# Power_Supply.net
KiCad netlist of a schematic drawn in Altium Designer
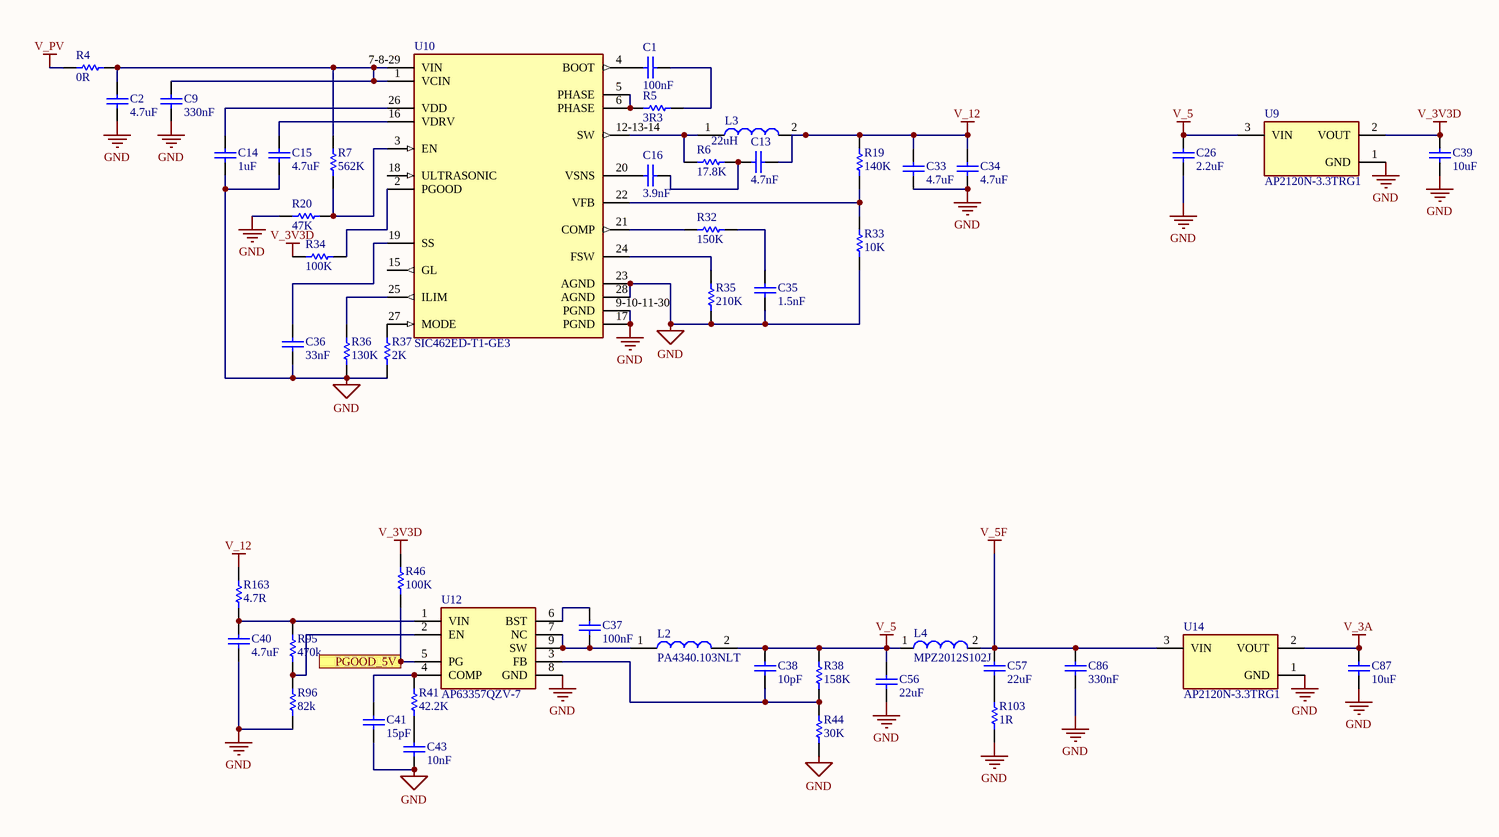
[diagram p0: Power_Supply.SchDoc]

(export (version "E")
  (design (tool "Eeschema 10.0.6"))
  (components
    (comp (ref "C1")
      (value "100nF")
      (footprint "CAPC1005X56X25NL10T15")
      (fields
        (field (name "MANUFACTURER") "AVX Interconnect / Elco")
        (field (name "PART NUMBER") "0402YC104KAT2A")
        (field (name "TOLERANCE") "10%")
      )
      (libsource (lib "Altium Content Vault") (part "CAP"))
    )
    (comp (ref "C2")
      (value "4.7uF")
      (footprint "CAPC3216X180X50NL20T25")
      (description "Chip Capacitor, 4.7 uF, +/- 10%, 50 V, -55 to 125 degC, 1206 (3216 Metric), RoHS, Tape and Reel")
      (fields (field (name "TOLERANCE") "10%") (field (name "MANUFACTURER") "AVX"))
      (libsource (lib "Altium Content Vault") (part "CAP-NP-2"))
    )
    (comp (ref "C9")
      (value "330nF")
      (footprint "CAPC2013X140X50NL20T25")
      (description "C0805C224K1RACAUTO")
      (fields (field (name "MANUFACTURER") "Kemet") (field (name "TOLERANCE") "10%"))
      (libsource (lib "Altium Content Vault") (part "CAP"))
    )
    (comp (ref "C13")
      (value "4.7nF")
      (footprint "CAPC1608X90X35NL10T15")
      (description "CAP CER 4700PF 50V X7R 0603")
      (fields (field (name "PART NUMBER") "GRM188R71H472KA01D") (field (name "MANUFACTURER") "Murata"))
      (libsource (lib "Altium Content Vault") (part "CAP"))
    )
    (comp (ref "C14")
      (value "1uF")
      (footprint "CAPC1608X90X35NL15T15")
      (description "SMD, 1 µF, 10 V, 0603 [Metrisch 1608], ± 10%, X7R")
      (fields (field (name "MANUFACTURER") "Kemet") (field (name "PART NUMBER") "C0603C105K8RACTU"))
      (libsource (lib "Altium Content Vault") (part "CAP"))
    )
    (comp (ref "C15")
      (value "4.7uF")
      (footprint "CAPC2013X152X50NL20T25")
      (fields
        (field (name "PART NUMBER") "0805YC475KAT2A")
        (field (name "MANUFACTURER") "AVX Interconnect / Elco")
        (field (name "TOLERANCE") "10%")
      )
      (libsource (lib "Altium Content Vault") (part "CAP"))
    )
    (comp (ref "C16")
      (value "3.9nF")
      (footprint "CAPC1608X90X35NL15T15")
      (fields
        (field (name "PART NUMBER") "06031C392KAT2A")
        (field (name "MANUFACTURER") "AVX Interconnect / Elco")
        (field (name "TOLERANCE") "10%")
      )
      (libsource (lib "Altium Content Vault") (part "CAP"))
    )
    (comp (ref "C26")
      (value "2.2uF")
      (footprint "CAPC2013X140X45NL15T25")
      (fields (field (name "PART NUMBER") "GRM21BR71A106KE51L") (field (name "MANUFACTURER") "Murata"))
      (libsource (lib "Altium Content Vault") (part "CAP"))
    )
    (comp (ref "C33")
      (value "4.7uF")
      (footprint "CAPC3216X180X50NL20T25")
      (description "Chip Capacitor, 4.7 uF, +/- 10%, 50 V, -55 to 125 degC, 1206 (3216 Metric), RoHS, Tape and Reel")
      (fields (field (name "TOLERANCE") "10%") (field (name "MANUFACTURER") "AVX"))
      (libsource (lib "Altium Content Vault") (part "CAP-NP-2"))
    )
    (comp (ref "C34")
      (value "4.7uF")
      (footprint "CAPC3216X180X50NL20T25")
      (description "Chip Capacitor, 4.7 uF, +/- 10%, 50 V, -55 to 125 degC, 1206 (3216 Metric), RoHS, Tape and Reel")
      (fields (field (name "TOLERANCE") "10%") (field (name "MANUFACTURER") "AVX"))
      (libsource (lib "Altium Content Vault") (part "CAP-NP-2"))
    )
    (comp (ref "C35")
      (value "1.5nF")
      (footprint "CAPC1608X90X35NL15T15")
      (fields
        (field (name "PART NUMBER") "06031C152JAT2A")
        (field (name "MANUFACTURER") "AVX Interconnect / Elco")
        (field (name "TOLERANCE") "5%")
      )
      (libsource (lib "Altium Content Vault") (part "CAP"))
    )
    (comp (ref "C36")
      (value "33nF")
      (footprint "CAPC1005X55X25NL05T10")
      (fields
        (field (name "PART NUMBER") "GRM155R71E333KA88D")
        (field (name "MANUFACTURER") "Murata")
        (field (name "TOLERANCE") "10%")
      )
      (libsource (lib "Altium Content Vault") (part "CAP"))
    )
    (comp (ref "C37")
      (value "100nF")
      (footprint "CAPC1005X56X25NL10T15")
      (fields
        (field (name "MANUFACTURER") "AVX Interconnect / Elco")
        (field (name "PART NUMBER") "0402YC104KAT2A")
        (field (name "TOLERANCE") "10%")
      )
      (libsource (lib "Altium Content Vault") (part "CAP"))
    )
    (comp (ref "C38")
      (value "10pF")
      (footprint "CAPC1005X56X25NL10T15")
      (fields
        (field (name "PART NUMBER") "04025A100DAT2A")
        (field (name "MANUFACTURER") "AVX Interconnect / Elco")
        (field (name "TOLERANCE") "5%")
      )
      (libsource (lib "Altium Content Vault") (part "CAP"))
    )
    (comp (ref "C39")
      (value "10uF")
      (footprint "CAPC2013X140X45NL15T25")
      (fields (field (name "PART NUMBER") "GRM21BR71A106KE51L") (field (name "MANUFACTURER") "Murata"))
      (libsource (lib "Altium Content Vault") (part "CAP"))
    )
    (comp (ref "C40")
      (value "4.7uF")
      (footprint "CAPC3216X180X50NL20T25")
      (description "Chip Capacitor, 4.7 uF, +/- 10%, 50 V, -55 to 125 degC, 1206 (3216 Metric), RoHS, Tape and Reel")
      (fields (field (name "TOLERANCE") "10%") (field (name "MANUFACTURER") "AVX"))
      (libsource (lib "Altium Content Vault") (part "CAP-NP-2"))
    )
    (comp (ref "C41")
      (value "15pF")
      (footprint "CAPC1005X56X25NL10T15")
      (description "Cap Ceramic 15pF 50V C0G 1% SMD 0402 125C Paper T/R")
      (fields
        (field (name "MANUFACTURER") "AVX Interconnect / Elco")
        (field (name "PART NUMBER") "04025A150FAT2A")
      )
      (libsource (lib "Altium Content Vault") (part "CAP"))
    )
    (comp (ref "C43")
      (value "10nF")
      (footprint "CAPC1005X56X25NL10T15")
      (fields
        (field (name "MANUFACTURER") "AVX Interconnect / Elco")
        (field (name "PART NUMBER") "04023C103JAT2A")
        (field (name "TOLERANCE") "5%")
      )
      (libsource (lib "Altium Content Vault") (part "CAP"))
    )
    (comp (ref "C56")
      (value "22uF")
      (footprint "CAPC1206(3216)190_N")
      (description "CAP 22uF 6.3V ±10% 1206 (3216 Metric) Thickness 1.9mm SMD")
      (fields (field (name "TOLERANCE") "Â±10%") (field (name "MANUFACTURER") "Kyocera AVX"))
      (libsource (lib "Altium Content Vault") (part "CAP"))
    )
    (comp (ref "C57")
      (value "22uF")
      (footprint "CAPC1206(3216)190_M")
      (description "CAP 22uF 6.3V ±10% 1206 (3216 Metric) Thickness 1.9mm SMD")
      (fields (field (name "TOLERANCE") "Â±10%") (field (name "MANUFACTURER") "Kyocera AVX"))
      (libsource (lib "Altium Content Vault") (part "CAP"))
    )
    (comp (ref "C86")
      (value "330nF")
      (footprint "CAPC2013X140X45NL15T25")
      (fields (field (name "PART NUMBER") "GRM21BR71A106KE51L") (field (name "MANUFACTURER") "Murata"))
      (libsource (lib "Altium Content Vault") (part "CAP"))
    )
    (comp (ref "C87")
      (value "10uF")
      (footprint "CAPC2013X140X45NL15T25")
      (fields (field (name "PART NUMBER") "GRM21BR71A106KE51L") (field (name "MANUFACTURER") "Murata"))
      (libsource (lib "Altium Content Vault") (part "CAP"))
    )
    (comp (ref "L2")
      (value "PA4340.103NLT")
      (footprint "SamacSys:INDPM6054X300N")
      (description "Inductor 10uH")
      (fields (field (name "ARROW PART NUMBER") "PA4340.472NLT"))
      (libsource (lib "*") (part "PA4340.472NLT"))
    )
    (comp (ref "L3")
      (value "22uH")
      (footprint "SamacSys:INDPM8680X400N")
      (description "Inductor 22uH")
      (fields
        (field (name "MANUFACTURER_PART_NUMBER") "MPX1D0840L220")
        (field (name "MOUSER PART NUMBER") "80-MPX1D0840L220")
      )
      (libsource (lib "*") (part "MPX1D0840L470"))
    )
    (comp (ref "L4")
      (value "MPZ2012S102J")
      (footprint "SMD-0805")
      (description "SMD EMI Suppression Ferrite Bead WE-CBF, Z = 1500 Ohm")
      (libsource (lib "Altium Content Vault") (part "PAS-IND-INDUCTOR-2"))
    )
    (comp (ref "R4")
      (value "0R")
      (footprint "RESC1608X55X25ML10T15")
      (description "Chip Resistor, 0 Ohm, +/- 5%, 0.1 W, -55 to 155 degC, 0603 (1608 Metric), RoHS, Tape and Reel")
      (fields (field (name "TOLERANCE") "5%") (field (name "MANUFACTURER") "Yageo"))
      (libsource (lib "Altium Content Vault") (part "RES-2"))
    )
    (comp (ref "R5")
      (value "3R3")
      (footprint "RESC1005X40X25NL05T10")
      (description "Res Thick Film 0402 3.3 Ohm 1% 1/16W ±200ppm/°C Molded SMD Paper T/R")
      (fields (field (name "MANUFACTURER") "Yageo / Phycomp") (field (name "PART NUMBER") "RC0402FR-073R3L"))
      (libsource (lib "Altium Content Vault") (part "RES"))
    )
    (comp (ref "R6")
      (value "17.8K")
      (footprint "RESC1608X55X30NL15T15")
      (description "RESISTOR, THICK FILM, 17.8KOHM, 0603, 100mW, ± 1%")
      (fields (field (name "PART NUMBER") "ERJ-3EKF1782V") (field (name "MANUFACTURER") "Panasonic"))
      (libsource (lib "Altium Content Vault") (part "RES"))
    )
    (comp (ref "R7")
      (value "562K")
      (footprint "RESC1609X50X30NL10T20")
      (description "RES, THICK FILM, 562K, 1%, 0.1W, 0603")
      (fields (field (name "PART NUMBER") "CRCW0603562KFKEA") (field (name "MANUFACTURER") "Vishay Dale"))
      (libsource (lib "Altium Content Vault") (part "RES"))
    )
    (comp (ref "R19")
      (value "140K")
      (footprint "RESC1005X40X25NL05T05")
      (description "SMD Chip Resistor, 0402 [1005 Metric], 140 kohm, ERJ2R Series, 50 V, Thick Film, 100 mW, 1%")
      (fields (field (name "PART NUMBER") "ERJ-2RKF1403X") (field (name "MANUFACTURER") "Panasonic"))
      (libsource (lib "Altium Content Vault") (part "RES"))
    )
    (comp (ref "R20")
      (value "47K")
      (footprint "RESC1608X55X30NL15T15")
      (description "Chip Resistor, 47 KOhm, +/- 1%, 0.1 W, -55 to 155 degC, 0603 (1608 Metric), RoHS, Tape and Reel")
      (fields
        (field (name "MANUFACTURER") "Panasonic")
        (field (name "MANUFACTURER PART NUMBER") "ERJ3EKF4702V")
      )
      (libsource (lib "Altium Content Vault") (part "RES-2"))
    )
    (comp (ref "R32")
      (value "150K")
      (footprint "RESC1005X40X25NL05T05")
      (description "RES, THICK FILM, 150K, 1%, 0.1W, 0402")
      (fields (field (name "MANUFACTURER") "Panasonic") (field (name "PART NUMBER") "ERJ-2RKF1503X"))
      (libsource (lib "Altium Content Vault") (part "RES"))
    )
    (comp (ref "R33")
      (value "10K")
      (footprint "RESC1005X40X25NL05T05")
      (description "Chip Resistor, 10 KOhm, +/- 1%, 0.1 W, -55 to 155 degC, 0402 (1005 Metric), RoHS, Tape and Reel")
      (fields (field (name "TOLERANCE") "1%") (field (name "MANUFACTURER") "Panasonic"))
      (libsource (lib "Altium Content Vault") (part "RES-2"))
    )
    (comp (ref "R34")
      (value "100K")
      (footprint "RESC1005X40X25NL05T10")
      (description "Res General Purpose Thick Film 0402 100K Ohm 1% 1/16W ±100ppm/°C Molded SMD Paper T/R")
      (fields (field (name "PART NUMBER") "RC0402FR-07100KL") (field (name "MANUFACTURER") "Yageo / Phycomp"))
      (libsource (lib "Altium Content Vault") (part "RES"))
    )
    (comp (ref "R35")
      (value "210K")
      (footprint "RESC1005X40X25NL05T05")
      (description "SMD Chip Resistor, Thick Film, 210 kohm, 50 V, 0402 [1005 Metric], 100 mW,  1%, ERJ2R Series")
      (fields (field (name "MANUFACTURER") "Panasonic") (field (name "PART NUMBER") "ERJ-2RKF2103X"))
      (libsource (lib "Altium Content Vault") (part "RES"))
    )
    (comp (ref "R36")
      (value "130K")
      (footprint "RESC1005X40X25NL05T10")
      (description "Res Thick Film 1.0 x 0.5 mm 130K Ohm 1% 0.063W(1/16W) 100ppm/ C Molded SMD Paper T/R")
      (fields (field (name "PART NUMBER") "RC0402FR-07130KL") (field (name "MANUFACTURER") "Yageo / Phycomp"))
      (libsource (lib "Altium Content Vault") (part "RES"))
    )
    (comp (ref "R37")
      (value "2K")
      (footprint "RESC1005X40X25NL05T05")
      (description "Chip Resistor, 2 KOhm, +/- 1%, 100 mW, -55 to 155 degC, 0402 (1005 Metric), RoHS, Tape and Reel")
      (fields (field (name "MANUFACTURER") "Basic Passives") (field (name "TOLERANCE") "1%"))
      (libsource (lib "Altium Content Vault") (part "RES-2"))
    )
    (comp (ref "R38")
      (value "158K")
      (footprint "RESC1005X40X25NL05T05")
      (description "RES SMD 158K OHM 1% 1/16W 0402")
      (fields (field (name "MANUFACTURER") "Vishay Dale") (field (name "PART NUMBER") "CRCW0402158KFKTD"))
      (libsource (lib "Altium Content Vault") (part "RES"))
    )
    (comp (ref "R41")
      (value "42.2K")
      (footprint "RESC1005X40X25NL05T05")
      (description "Surface Mount Chip Resistor, Thick Film, AEC-Q200 CRCW Series, 42.2 kohm, 63 mW,  1%, 50 V")
      (fields (field (name "PART NUMBER") "CRCW040242K2FKED") (field (name "MANUFACTURER") "Vishay Dale"))
      (libsource (lib "Altium Content Vault") (part "RES"))
    )
    (comp (ref "R44")
      (value "30K")
      (footprint "RESC1005X40X25NL05T05")
      (description "Res Thick Film 0402 30K Ohm 1% 0.063W(1/16W) ±100ppm/C Molded SMD Automotive Paper T/R")
      (fields (field (name "PART NUMBER") "CRCW040230K0FKED") (field (name "MANUFACTURER") "Vishay Dale"))
      (libsource (lib "Altium Content Vault") (part "RES"))
    )
    (comp (ref "R46")
      (value "100K")
      (footprint "RESC1005X40X25NL05T10")
      (description "Res General Purpose Thick Film 0402 100K Ohm 1% 1/16W ±100ppm/°C Molded SMD Paper T/R")
      (fields (field (name "PART NUMBER") "RC0402FR-07100KL") (field (name "MANUFACTURER") "Yageo / Phycomp"))
      (libsource (lib "Altium Content Vault") (part "RES"))
    )
    (comp (ref "R95")
      (value "470k")
      (footprint "RESC1005X40X25NL05T05")
      (description "ERJ-2RKF4993X")
      (fields (field (name "MANUFACTURER") "Panasonic") (field (name "TOLERANCE") "1%"))
      (libsource (lib "Altium Content Vault") (part "RES"))
    )
    (comp (ref "R96")
      (value "82k")
      (footprint "RESC1005X40X25NL05T05")
      (description "ERJ-2RKF4993X")
      (fields (field (name "MANUFACTURER") "Panasonic") (field (name "TOLERANCE") "1%"))
      (libsource (lib "Altium Content Vault") (part "RES"))
    )
    (comp (ref "R103")
      (value "1R")
      (footprint "RESC2012X70N")
      (description "Chip Resistor, 0 Ohm, +/- 5%, 125 mW, -55 to 155 degC, 0805 (2012 Metric), RoHS, Tape and Reel")
      (fields (field (name "PARTNUMBER") "ERJ-6GEY0R00V") (field (name "MANUFACTURER") "Basic Passives"))
      (libsource (lib "PBL - Resistors") (part "RES-2"))
    )
    (comp (ref "R163")
      (value "4.7R")
      (footprint "RESC2013X70X40LL20T20")
      (description "Chip Resistor, 4.7 Ohm, +/- 1%, 125 mW, -55 to 125 degC, 0805 (2012 Metric), RoHS, Tape and Reel")
      (fields (field (name "TOLERANCE") "1%") (field (name "PARTNUMBER") "ERJ-6RQF4R7V"))
      (libsource (lib "Altium Content Vault") (part "RES-2"))
    )
    (comp (ref "U9")
      (value "AP2120N-3.3TRG1")
      (footprint "FP-SOT23-MFG")
      (description "IC REG LINEAR 3.3V 150MA SOT23")
      (fields
        (field (name "MANUFACTURER") "Diodes Inc.")
        (field (name "OCTOPART") "https://octopart.com/ap2120n-3.3trg1-diodes+inc.-30954573")
      )
      (libsource (lib "Altium Content Vault") (part "340b21d0b7389e2ba8b62ca99e39354"))
    )
    (comp (ref "U10")
      (value "SIC462ED-T1-GE3")
      (footprint "FP-T18-0594-MFG")
      (description "IC REG BUCK ADJ 6A MLP55-27")
      (fields
        (field (name "MANUFACTURER") "Vishay")
        (field (name "OCTOPART") "https://octopart.com/sic462ed-t1-ge3-vishay-76790763")
      )
      (libsource (lib "Altium Content Vault") (part "92a46bbdb5b7b3ea9c407102cc13196"))
    )
    (comp (ref "U12")
      (value "AP63357QZV-7")
      (footprint "SamacSys:AP63357QZV7")
      (description "Integrated Circuit")
      (fields (field (name "MOUSER PART NUMBER") "621-AP63357QZV-7"))
      (libsource (lib "*") (part "AP63357QZV-7"))
    )
    (comp (ref "U14")
      (value "AP2120N-3.3TRG1")
      (footprint "FP-SOT23-MFG")
      (description "IC REG LINEAR 3.3V 150MA SOT23")
      (fields
        (field (name "MANUFACTURER") "Diodes Inc.")
        (field (name "OCTOPART") "https://octopart.com/ap2120n-3.3trg1-diodes+inc.-30954573")
      )
      (libsource (lib "Altium Content Vault") (part "340b21d0b7389e2ba8b62ca99e39354"))
    )
  )
  (nets
    (net (code "1") (name "/PGOOD_5V") (class "Default")
      (node (ref "R46") (pin "1") (pinfunction "1_1") (pintype "passive"))
      (node (ref "U12") (pin "5") (pinfunction "PG_5") (pintype "passive"))
    )
    (net (code "2") (name "GND") (class "Default")
      (node (ref "C14") (pin "1") (pinfunction "1_1") (pintype "passive"))
      (node (ref "C15") (pin "1") (pinfunction "1_1") (pintype "passive"))
      (node (ref "C2") (pin "1") (pinfunction "1_1") (pintype "passive"))
      (node (ref "C26") (pin "1") (pinfunction "1_1") (pintype "passive"))
      (node (ref "C33") (pin "1") (pinfunction "1_1") (pintype "passive"))
      (node (ref "C34") (pin "1") (pinfunction "1_1") (pintype "passive"))
      (node (ref "C35") (pin "1") (pinfunction "1_1") (pintype "passive"))
      (node (ref "C36") (pin "1") (pinfunction "1_1") (pintype "passive"))
      (node (ref "C39") (pin "1") (pinfunction "1_1") (pintype "passive"))
      (node (ref "C40") (pin "1") (pinfunction "1_1") (pintype "passive"))
      (node (ref "C41") (pin "1") (pinfunction "1_1") (pintype "passive"))
      (node (ref "C43") (pin "1") (pinfunction "1_1") (pintype "passive"))
      (node (ref "C56") (pin "1") (pinfunction "1_1") (pintype "passive"))
      (node (ref "C86") (pin "1") (pinfunction "1_1") (pintype "passive"))
      (node (ref "C87") (pin "1") (pinfunction "1_1") (pintype "passive"))
      (node (ref "C9") (pin "1") (pinfunction "1_1") (pintype "passive"))
      (node (ref "R103") (pin "1") (pinfunction "1_1") (pintype "passive"))
      (node (ref "R20") (pin "1") (pinfunction "1_1") (pintype "passive"))
      (node (ref "R33") (pin "1") (pinfunction "1_1") (pintype "passive"))
      (node (ref "R35") (pin "1") (pinfunction "1_1") (pintype "passive"))
      (node (ref "R36") (pin "1") (pinfunction "1_1") (pintype "passive"))
      (node (ref "R37") (pin "1") (pinfunction "1_1") (pintype "passive"))
      (node (ref "R44") (pin "1") (pinfunction "1_1") (pintype "passive"))
      (node (ref "R96") (pin "1") (pinfunction "1_1") (pintype "passive"))
      (node (ref "U10") (pin "17") (pinfunction "PGND_17") (pintype "power_in"))
      (node (ref "U10") (pin "23") (pinfunction "AGND_23") (pintype "power_in"))
      (node (ref "U10") (pin "28") (pinfunction "AGND_28") (pintype "power_in"))
      (node (ref "U10") (pin "9-10-11-30") (pinfunction "PGND_9-10-11-30") (pintype "power_in"))
      (node (ref "U12") (pin "8") (pinfunction "GND_8") (pintype "passive"))
      (node (ref "U14") (pin "1") (pinfunction "GND_1") (pintype "power_in"))
      (node (ref "U9") (pin "1") (pinfunction "GND_1") (pintype "power_in"))
    )
    (net (code "3") (name "Net-(C1-Pad2)") (class "Default")
      (node (ref "C1") (pin "2") (pinfunction "2_2") (pintype "passive"))
      (node (ref "R5") (pin "2") (pinfunction "2_2") (pintype "passive"))
    )
    (net (code "4") (name "Net-(C13-Pad1)") (class "Default")
      (node (ref "C13") (pin "1") (pinfunction "1_1") (pintype "passive"))
      (node (ref "C16") (pin "2") (pinfunction "2_2") (pintype "passive"))
      (node (ref "R6") (pin "2") (pinfunction "2_2") (pintype "passive"))
    )
    (net (code "5") (name "Net-(C35-Pad2)") (class "Default")
      (node (ref "C35") (pin "2") (pinfunction "2_2") (pintype "passive"))
      (node (ref "R32") (pin "1") (pinfunction "1_1") (pintype "passive"))
    )
    (net (code "6") (name "Net-(C43-Pad2)") (class "Default")
      (node (ref "C43") (pin "2") (pinfunction "2_2") (pintype "passive"))
      (node (ref "R41") (pin "1") (pinfunction "1_1") (pintype "passive"))
    )
    (net (code "7") (name "Net-(C57-Pad2)") (class "Default")
      (node (ref "C57") (pin "2") (pinfunction "2_2") (pintype "passive"))
      (node (ref "R103") (pin "2") (pinfunction "2_2") (pintype "passive"))
    )
    (net (code "8") (name "Net-(R5-Pad1)") (class "Default")
      (node (ref "R5") (pin "1") (pinfunction "1_1") (pintype "passive"))
      (node (ref "U10") (pin "5") (pinfunction "PHASE_5") (pintype "passive"))
      (node (ref "U10") (pin "6") (pinfunction "PHASE_6") (pintype "passive"))
    )
    (net (code "9") (name "Net-(U10-BOOT)") (class "Default")
      (node (ref "C1") (pin "1") (pinfunction "1_1") (pintype "passive"))
      (node (ref "U10") (pin "4") (pinfunction "BOOT_4") (pintype "output"))
    )
    (net (code "10") (name "Net-(U10-COMP)") (class "Default")
      (node (ref "R32") (pin "2") (pinfunction "2_2") (pintype "passive"))
      (node (ref "U10") (pin "21") (pinfunction "COMP_21") (pintype "output"))
    )
    (net (code "11") (name "Net-(U10-EN)") (class "Default")
      (node (ref "R20") (pin "2") (pinfunction "2_2") (pintype "passive"))
      (node (ref "R7") (pin "1") (pinfunction "1_1") (pintype "passive"))
      (node (ref "U10") (pin "3") (pinfunction "EN_3") (pintype "input"))
    )
    (net (code "12") (name "Net-(U10-FSW)") (class "Default")
      (node (ref "R35") (pin "2") (pinfunction "2_2") (pintype "passive"))
      (node (ref "U10") (pin "24") (pinfunction "FSW_24") (pintype "passive"))
    )
    (net (code "13") (name "Net-(U10-ILIM)") (class "Default")
      (node (ref "R36") (pin "2") (pinfunction "2_2") (pintype "passive"))
      (node (ref "U10") (pin "25") (pinfunction "ILIM_25") (pintype "output"))
    )
    (net (code "14") (name "Net-(U10-MODE)") (class "Default")
      (node (ref "R37") (pin "2") (pinfunction "2_2") (pintype "passive"))
      (node (ref "U10") (pin "27") (pinfunction "MODE_27") (pintype "input"))
    )
    (net (code "15") (name "Net-(U10-PGOOD)") (class "Default")
      (node (ref "R34") (pin "2") (pinfunction "2_2") (pintype "passive"))
      (node (ref "U10") (pin "2") (pinfunction "PGOOD_2") (pintype "open_collector"))
    )
    (net (code "16") (name "Net-(U10-SS)") (class "Default")
      (node (ref "C36") (pin "2") (pinfunction "2_2") (pintype "passive"))
      (node (ref "U10") (pin "19") (pinfunction "SS_19") (pintype "passive"))
    )
    (net (code "17") (name "Net-(U10-SW)") (class "Default")
      (node (ref "L3") (pin "1") (pinfunction "1_1") (pintype "passive"))
      (node (ref "R6") (pin "1") (pinfunction "1_1") (pintype "passive"))
      (node (ref "U10") (pin "12-13-14") (pinfunction "SW_12-13-14") (pintype "output"))
    )
    (net (code "18") (name "Net-(U10-VCIN)") (class "Default")
      (node (ref "C2") (pin "2") (pinfunction "2_2") (pintype "passive"))
      (node (ref "C9") (pin "2") (pinfunction "2_2") (pintype "passive"))
      (node (ref "R4") (pin "1") (pinfunction "1_1") (pintype "passive"))
      (node (ref "R7") (pin "2") (pinfunction "2_2") (pintype "passive"))
      (node (ref "U10") (pin "1") (pinfunction "VCIN_1") (pintype "power_in"))
      (node (ref "U10") (pin "7-8-29") (pinfunction "VIN_7-8-29") (pintype "power_in"))
    )
    (net (code "19") (name "Net-(U10-VDD)") (class "Default")
      (node (ref "C14") (pin "2") (pinfunction "2_2") (pintype "passive"))
      (node (ref "U10") (pin "26") (pinfunction "VDD_26") (pintype "power_in"))
    )
    (net (code "20") (name "Net-(U10-VDRV)") (class "Default")
      (node (ref "C15") (pin "2") (pinfunction "2_2") (pintype "passive"))
      (node (ref "U10") (pin "16") (pinfunction "VDRV_16") (pintype "power_in"))
    )
    (net (code "21") (name "Net-(U10-VFB)") (class "Default")
      (node (ref "R19") (pin "1") (pinfunction "1_1") (pintype "passive"))
      (node (ref "R33") (pin "2") (pinfunction "2_2") (pintype "passive"))
      (node (ref "U10") (pin "22") (pinfunction "VFB_22") (pintype "passive"))
    )
    (net (code "22") (name "Net-(U10-VSNS)") (class "Default")
      (node (ref "C16") (pin "1") (pinfunction "1_1") (pintype "passive"))
      (node (ref "U10") (pin "20") (pinfunction "VSNS_20") (pintype "power_in"))
    )
    (net (code "23") (name "Net-(U12-BST)") (class "Default")
      (node (ref "C37") (pin "2") (pinfunction "2_2") (pintype "passive"))
      (node (ref "U12") (pin "6") (pinfunction "BST_6") (pintype "passive"))
    )
    (net (code "24") (name "Net-(U12-COMP)") (class "Default")
      (node (ref "C41") (pin "2") (pinfunction "2_2") (pintype "passive"))
      (node (ref "R41") (pin "2") (pinfunction "2_2") (pintype "passive"))
      (node (ref "U12") (pin "4") (pinfunction "COMP_4") (pintype "passive"))
    )
    (net (code "25") (name "Net-(U12-EN)") (class "Default")
      (node (ref "R95") (pin "1") (pinfunction "1_1") (pintype "passive"))
      (node (ref "R96") (pin "2") (pinfunction "2_2") (pintype "passive"))
      (node (ref "U12") (pin "2") (pinfunction "EN_2") (pintype "passive"))
    )
    (net (code "26") (name "Net-(U12-FB)") (class "Default")
      (node (ref "C38") (pin "1") (pinfunction "1_1") (pintype "passive"))
      (node (ref "R38") (pin "1") (pinfunction "1_1") (pintype "passive"))
      (node (ref "R44") (pin "2") (pinfunction "2_2") (pintype "passive"))
      (node (ref "U12") (pin "3") (pinfunction "FB_3") (pintype "passive"))
    )
    (net (code "27") (name "Net-(U12-NC)") (class "Default")
      (node (ref "C37") (pin "1") (pinfunction "1_1") (pintype "passive"))
      (node (ref "L2") (pin "1") (pinfunction "1_1") (pintype "passive"))
      (node (ref "U12") (pin "7") (pinfunction "NC_7") (pintype "passive"))
      (node (ref "U12") (pin "9") (pinfunction "SW_9") (pintype "passive"))
    )
    (net (code "28") (name "Net-(U12-VIN)") (class "Default")
      (node (ref "C40") (pin "2") (pinfunction "2_2") (pintype "passive"))
      (node (ref "R163") (pin "1") (pinfunction "1_1") (pintype "passive"))
      (node (ref "R95") (pin "2") (pinfunction "2_2") (pintype "passive"))
      (node (ref "U12") (pin "1") (pinfunction "VIN_1") (pintype "passive"))
    )
    (net (code "29") (name "V_3A") (class "Default")
      (node (ref "C87") (pin "2") (pinfunction "2_2") (pintype "passive"))
      (node (ref "U14") (pin "2") (pinfunction "VOUT_2") (pintype "power_in"))
    )
    (net (code "30") (name "V_3V3D") (class "Default")
      (node (ref "C39") (pin "2") (pinfunction "2_2") (pintype "passive"))
      (node (ref "R34") (pin "1") (pinfunction "1_1") (pintype "passive"))
      (node (ref "R46") (pin "2") (pinfunction "2_2") (pintype "passive"))
      (node (ref "U9") (pin "2") (pinfunction "VOUT_2") (pintype "power_in"))
    )
    (net (code "31") (name "V_5") (class "Default")
      (node (ref "C26") (pin "2") (pinfunction "2_2") (pintype "passive"))
      (node (ref "C38") (pin "2") (pinfunction "2_2") (pintype "passive"))
      (node (ref "C56") (pin "2") (pinfunction "2_2") (pintype "passive"))
      (node (ref "L2") (pin "2") (pinfunction "2_2") (pintype "passive"))
      (node (ref "L4") (pin "1") (pinfunction "1_1") (pintype "passive"))
      (node (ref "R38") (pin "2") (pinfunction "2_2") (pintype "passive"))
      (node (ref "U9") (pin "3") (pinfunction "VIN_3") (pintype "power_in"))
    )
    (net (code "32") (name "V_5F") (class "Default")
      (node (ref "C57") (pin "1") (pinfunction "1_1") (pintype "passive"))
      (node (ref "C86") (pin "2") (pinfunction "2_2") (pintype "passive"))
      (node (ref "L4") (pin "2") (pinfunction "2_2") (pintype "passive"))
      (node (ref "U14") (pin "3") (pinfunction "VIN_3") (pintype "power_in"))
    )
    (net (code "33") (name "V_12") (class "Default")
      (node (ref "C13") (pin "2") (pinfunction "2_2") (pintype "passive"))
      (node (ref "C33") (pin "2") (pinfunction "2_2") (pintype "passive"))
      (node (ref "C34") (pin "2") (pinfunction "2_2") (pintype "passive"))
      (node (ref "L3") (pin "2") (pinfunction "2_2") (pintype "passive"))
      (node (ref "R163") (pin "2") (pinfunction "2_2") (pintype "passive"))
      (node (ref "R19") (pin "2") (pinfunction "2_2") (pintype "passive"))
    )
    (net (code "34") (name "V_PV") (class "Default")
      (node (ref "R4") (pin "2") (pinfunction "2_2") (pintype "passive"))
    )
    (net (code "35") (name "unconnected-(U10-GL-Pad15)") (class "Default")
      (node (ref "U10") (pin "15") (pinfunction "GL_15") (pintype "output"))
    )
    (net (code "36") (name "unconnected-(U10-ULTRASONIC-Pad18)") (class "Default")
      (node (ref "U10") (pin "18") (pinfunction "ULTRASONIC_18") (pintype "input"))
    )
  )
)
